# FYP_Schematics.net
KiCad netlist of a schematic drawn in EasyEDA Pro
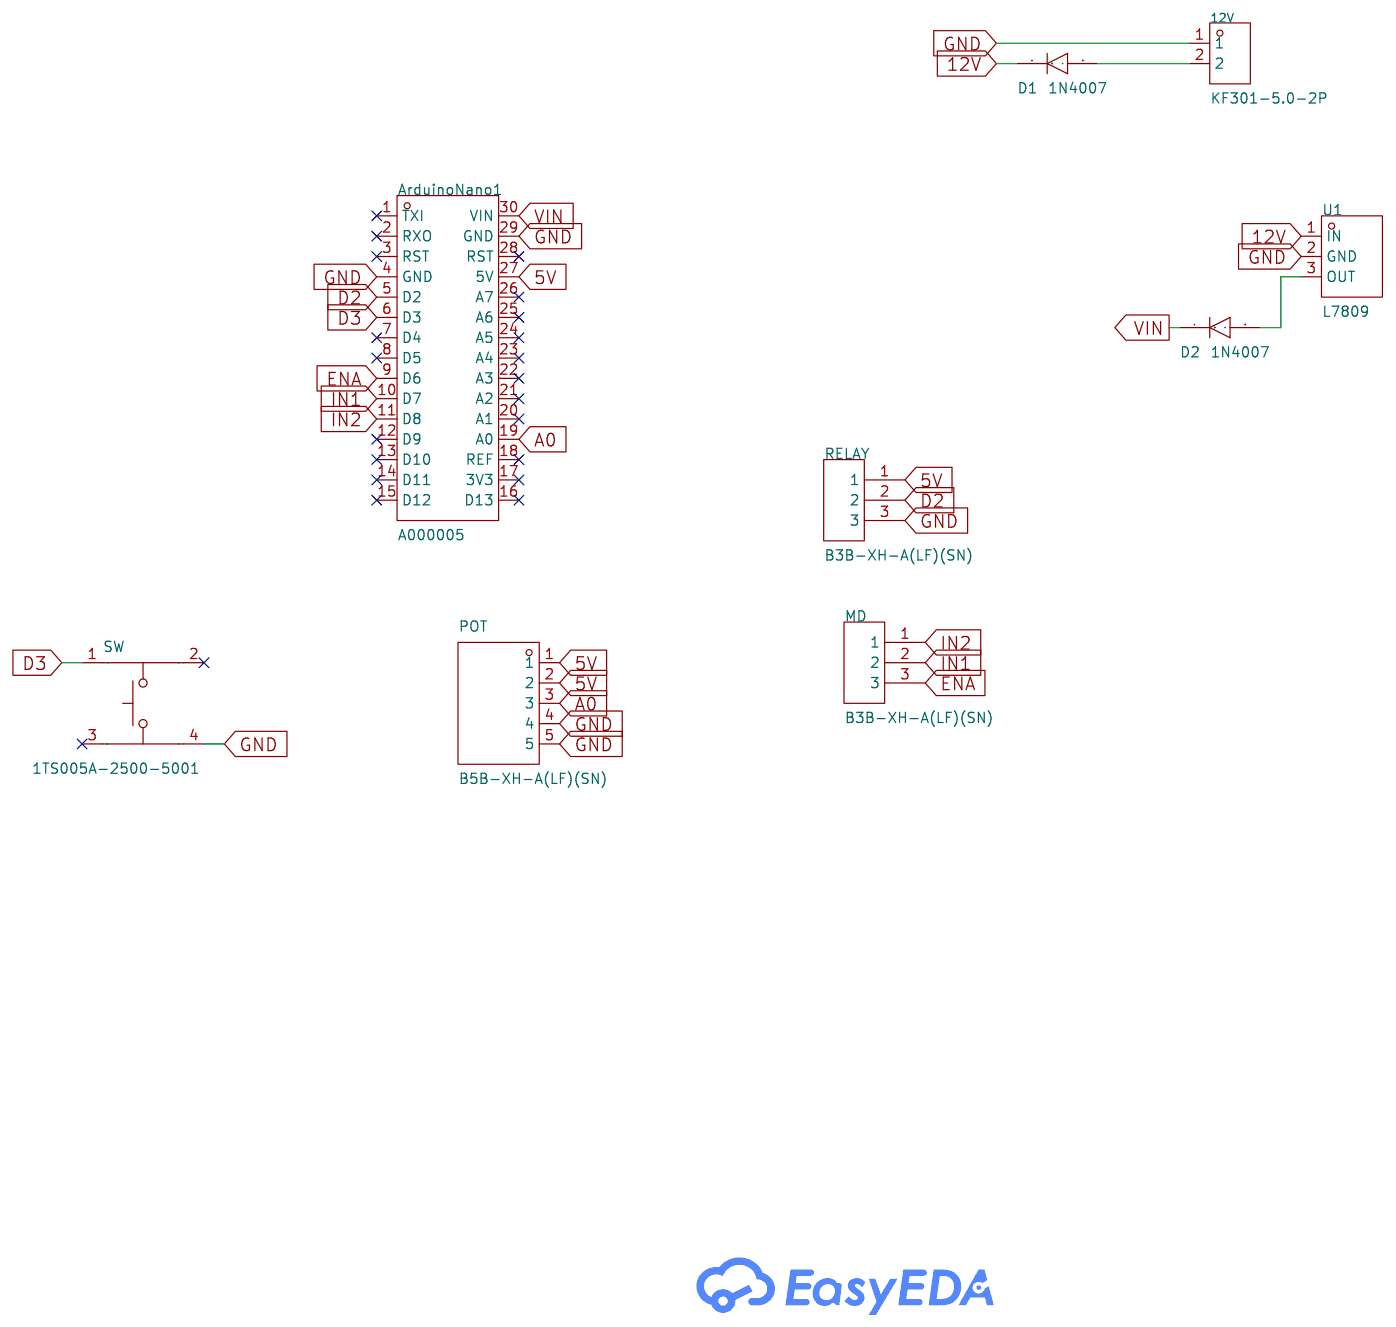
[diagram p0: schematic sheet]

(export (version "E")
  (design (tool "Eeschema 10.0.6"))
  (components
    (comp (ref "12V")
      (value "KF301-5.0-2P")
      (footprint "easyedapro:CONN-TH_P5.00_KF301-5.0-2P")
      (fields (field (name "Manufacturer") "KEFA(科发)"))
      (libsource (lib "easyedapro") (part "KF301-5.0-2P"))
    )
    (comp (ref "ArduinoNano1")
      (value "A000005")
      (footprint "easyedapro:COMM-TH_A000005")
      (fields (field (name "Manufacturer") "arduino"))
      (libsource (lib "easyedapro") (part "A000005"))
    )
    (comp (ref "D1")
      (value "1N4007")
      (footprint "easyedapro:DO-41_BD2.4-L4.7-P8.70-D0.9-RD")
      (fields (field (name "Manufacturer") "星海"))
      (libsource (lib "easyedapro") (part "1N4007-C84641"))
    )
    (comp (ref "D2")
      (value "1N4007")
      (footprint "easyedapro:DO-41_BD2.4-L4.7-P8.70-D0.9-RD")
      (fields (field (name "Manufacturer") "星海"))
      (libsource (lib "easyedapro") (part "1N4007-C84641"))
    )
    (comp (ref "MD")
      (value "B3B-XH-A(LF)(SN)")
      (footprint "easyedapro:CONN-TH_3P-P2.50_A2501WV2-3P")
      (fields (field (name "Manufacturer") "JST"))
      (libsource (lib "easyedapro") (part "B3B-XH-A(LF)(SN)"))
    )
    (comp (ref "POT")
      (value "B5B-XH-A(LF)(SN)")
      (footprint "easyedapro:CONN-TH_B5B-XH-A-LF-SN")
      (fields (field (name "Manufacturer") "JST"))
      (libsource (lib "easyedapro") (part "B5B-XH-A (LF)(SN)"))
    )
    (comp (ref "RELAY")
      (value "B3B-XH-A(LF)(SN)")
      (footprint "easyedapro:CONN-TH_3P-P2.50_A2501WV2-3P")
      (fields (field (name "Manufacturer") "JST"))
      (libsource (lib "easyedapro") (part "B3B-XH-A(LF)(SN)"))
    )
    (comp (ref "SW")
      (value "1TS005A-2500-5001")
      (footprint "easyedapro:SW-TH_4P-L6.0-W6.0-P3.90-LS6.5")
      (fields (field (name "Manufacturer") "HYP(鸿源精密)"))
      (libsource (lib "easyedapro") (part "1TS005A-2500-5001"))
    )
    (comp (ref "U1")
      (value "L7809")
      (footprint "easyedapro:TO-220-3_L10.0-W4.5-P2.54-L")
      (fields (field (name "Manufacturer") "PUOLOP(迪浦)"))
      (libsource (lib "easyedapro") (part "L7809"))
    )
  )
  (nets
    (net (code "1") (name "5V") (class "Default")
      (node (ref "ArduinoNano1") (pin "27") (pinfunction "5V_27") (pintype "unspecified"))
      (node (ref "POT") (pin "1") (pinfunction "1_1") (pintype "unspecified"))
      (node (ref "POT") (pin "2") (pinfunction "2_2") (pintype "unspecified"))
      (node (ref "RELAY") (pin "1") (pinfunction "1_1") (pintype "unspecified"))
    )
    (net (code "2") (name "12V") (class "Default")
      (node (ref "D1") (pin "1") (pinfunction "C_1") (pintype "unspecified"))
      (node (ref "U1") (pin "1") (pinfunction "IN_1") (pintype "unspecified"))
    )
    (net (code "3") (name "A0") (class "Default")
      (node (ref "ArduinoNano1") (pin "19") (pinfunction "A0_19") (pintype "unspecified"))
      (node (ref "POT") (pin "3") (pinfunction "3_3") (pintype "unspecified"))
    )
    (net (code "4") (name "D2") (class "Default")
      (node (ref "ArduinoNano1") (pin "5") (pinfunction "D2_5") (pintype "unspecified"))
      (node (ref "RELAY") (pin "2") (pinfunction "2_2") (pintype "unspecified"))
    )
    (net (code "5") (name "D3") (class "Default")
      (node (ref "ArduinoNano1") (pin "6") (pinfunction "D3_6") (pintype "unspecified"))
      (node (ref "SW") (pin "1") (pinfunction "1_1") (pintype "input"))
    )
    (net (code "6") (name "ENA") (class "Default")
      (node (ref "ArduinoNano1") (pin "9") (pinfunction "D6_9") (pintype "unspecified"))
      (node (ref "MD") (pin "3") (pinfunction "3_3") (pintype "unspecified"))
    )
    (net (code "7") (name "GND") (class "Default")
      (node (ref "12V") (pin "1") (pinfunction "1_1") (pintype "input"))
      (node (ref "ArduinoNano1") (pin "29") (pinfunction "GND_29") (pintype "unspecified"))
      (node (ref "ArduinoNano1") (pin "4") (pinfunction "GND_4") (pintype "unspecified"))
      (node (ref "POT") (pin "4") (pinfunction "4_4") (pintype "unspecified"))
      (node (ref "POT") (pin "5") (pinfunction "5_5") (pintype "unspecified"))
      (node (ref "RELAY") (pin "3") (pinfunction "3_3") (pintype "unspecified"))
      (node (ref "SW") (pin "4") (pinfunction "4_4") (pintype "input"))
      (node (ref "U1") (pin "2") (pinfunction "GND_2") (pintype "unspecified"))
    )
    (net (code "8") (name "IN1") (class "Default")
      (node (ref "ArduinoNano1") (pin "10") (pinfunction "D7_10") (pintype "unspecified"))
      (node (ref "MD") (pin "2") (pinfunction "2_2") (pintype "unspecified"))
    )
    (net (code "9") (name "IN2") (class "Default")
      (node (ref "ArduinoNano1") (pin "11") (pinfunction "D8_11") (pintype "unspecified"))
      (node (ref "MD") (pin "1") (pinfunction "1_1") (pintype "unspecified"))
    )
    (net (code "10") (name "Net-(D1-A)") (class "Default")
      (node (ref "12V") (pin "2") (pinfunction "2_2") (pintype "input"))
      (node (ref "D1") (pin "2") (pinfunction "A_2") (pintype "unspecified"))
    )
    (net (code "11") (name "Net-(D2-A)") (class "Default")
      (node (ref "D2") (pin "2") (pinfunction "A_2") (pintype "unspecified"))
      (node (ref "U1") (pin "3") (pinfunction "OUT_3") (pintype "unspecified"))
    )
    (net (code "12") (name "VIN") (class "Default")
      (node (ref "ArduinoNano1") (pin "30") (pinfunction "VIN_30") (pintype "unspecified"))
      (node (ref "D2") (pin "1") (pinfunction "C_1") (pintype "unspecified"))
    )
    (net (code "13") (name "unconnected-(ArduinoNano1-3V3-Pad17)") (class "Default")
      (node (ref "ArduinoNano1") (pin "17") (pinfunction "3V3_17") (pintype "unspecified+no_connect"))
    )
    (net (code "14") (name "unconnected-(ArduinoNano1-A1-Pad20)") (class "Default")
      (node (ref "ArduinoNano1") (pin "20") (pinfunction "A1_20") (pintype "unspecified+no_connect"))
    )
    (net (code "15") (name "unconnected-(ArduinoNano1-A2-Pad21)") (class "Default")
      (node (ref "ArduinoNano1") (pin "21") (pinfunction "A2_21") (pintype "unspecified+no_connect"))
    )
    (net (code "16") (name "unconnected-(ArduinoNano1-A3-Pad22)") (class "Default")
      (node (ref "ArduinoNano1") (pin "22") (pinfunction "A3_22") (pintype "unspecified+no_connect"))
    )
    (net (code "17") (name "unconnected-(ArduinoNano1-A4-Pad23)") (class "Default")
      (node (ref "ArduinoNano1") (pin "23") (pinfunction "A4_23") (pintype "unspecified+no_connect"))
    )
    (net (code "18") (name "unconnected-(ArduinoNano1-A5-Pad24)") (class "Default")
      (node (ref "ArduinoNano1") (pin "24") (pinfunction "A5_24") (pintype "unspecified+no_connect"))
    )
    (net (code "19") (name "unconnected-(ArduinoNano1-A6-Pad25)") (class "Default")
      (node (ref "ArduinoNano1") (pin "25") (pinfunction "A6_25") (pintype "unspecified+no_connect"))
    )
    (net (code "20") (name "unconnected-(ArduinoNano1-A7-Pad26)") (class "Default")
      (node (ref "ArduinoNano1") (pin "26") (pinfunction "A7_26") (pintype "unspecified+no_connect"))
    )
    (net (code "21") (name "unconnected-(ArduinoNano1-D4-Pad7)") (class "Default")
      (node (ref "ArduinoNano1") (pin "7") (pinfunction "D4_7") (pintype "unspecified+no_connect"))
    )
    (net (code "22") (name "unconnected-(ArduinoNano1-D5-Pad8)") (class "Default")
      (node (ref "ArduinoNano1") (pin "8") (pinfunction "D5_8") (pintype "unspecified+no_connect"))
    )
    (net (code "23") (name "unconnected-(ArduinoNano1-D9-Pad12)") (class "Default")
      (node (ref "ArduinoNano1") (pin "12") (pinfunction "D9_12") (pintype "unspecified+no_connect"))
    )
    (net (code "24") (name "unconnected-(ArduinoNano1-D10-Pad13)") (class "Default")
      (node (ref "ArduinoNano1") (pin "13") (pinfunction "D10_13") (pintype "unspecified+no_connect"))
    )
    (net (code "25") (name "unconnected-(ArduinoNano1-D11-Pad14)") (class "Default")
      (node (ref "ArduinoNano1") (pin "14") (pinfunction "D11_14") (pintype "unspecified+no_connect"))
    )
    (net (code "26") (name "unconnected-(ArduinoNano1-D12-Pad15)") (class "Default")
      (node (ref "ArduinoNano1") (pin "15") (pinfunction "D12_15") (pintype "unspecified+no_connect"))
    )
    (net (code "27") (name "unconnected-(ArduinoNano1-D13-Pad16)") (class "Default")
      (node (ref "ArduinoNano1") (pin "16") (pinfunction "D13_16") (pintype "unspecified+no_connect"))
    )
    (net (code "28") (name "unconnected-(ArduinoNano1-REF-Pad18)") (class "Default")
      (node (ref "ArduinoNano1") (pin "18") (pinfunction "REF_18") (pintype "unspecified+no_connect"))
    )
    (net (code "29") (name "unconnected-(ArduinoNano1-RST-Pad3)") (class "Default")
      (node (ref "ArduinoNano1") (pin "3") (pinfunction "RST_3") (pintype "unspecified+no_connect"))
    )
    (net (code "30") (name "unconnected-(ArduinoNano1-RST-Pad28)") (class "Default")
      (node (ref "ArduinoNano1") (pin "28") (pinfunction "RST_28") (pintype "unspecified+no_connect"))
    )
    (net (code "31") (name "unconnected-(ArduinoNano1-RXO-Pad2)") (class "Default")
      (node (ref "ArduinoNano1") (pin "2") (pinfunction "RXO_2") (pintype "unspecified+no_connect"))
    )
    (net (code "32") (name "unconnected-(ArduinoNano1-TXI-Pad1)") (class "Default")
      (node (ref "ArduinoNano1") (pin "1") (pinfunction "TXI_1") (pintype "unspecified+no_connect"))
    )
    (net (code "33") (name "unconnected-(SW-Pad2)") (class "Default")
      (node (ref "SW") (pin "2") (pinfunction "2_2") (pintype "input+no_connect"))
    )
    (net (code "34") (name "unconnected-(SW-Pad3)") (class "Default")
      (node (ref "SW") (pin "3") (pinfunction "3_3") (pintype "input+no_connect"))
    )
  )
)
